# ST_LINK_V2.net
KiCad netlist of a schematic drawn in Altium Designer
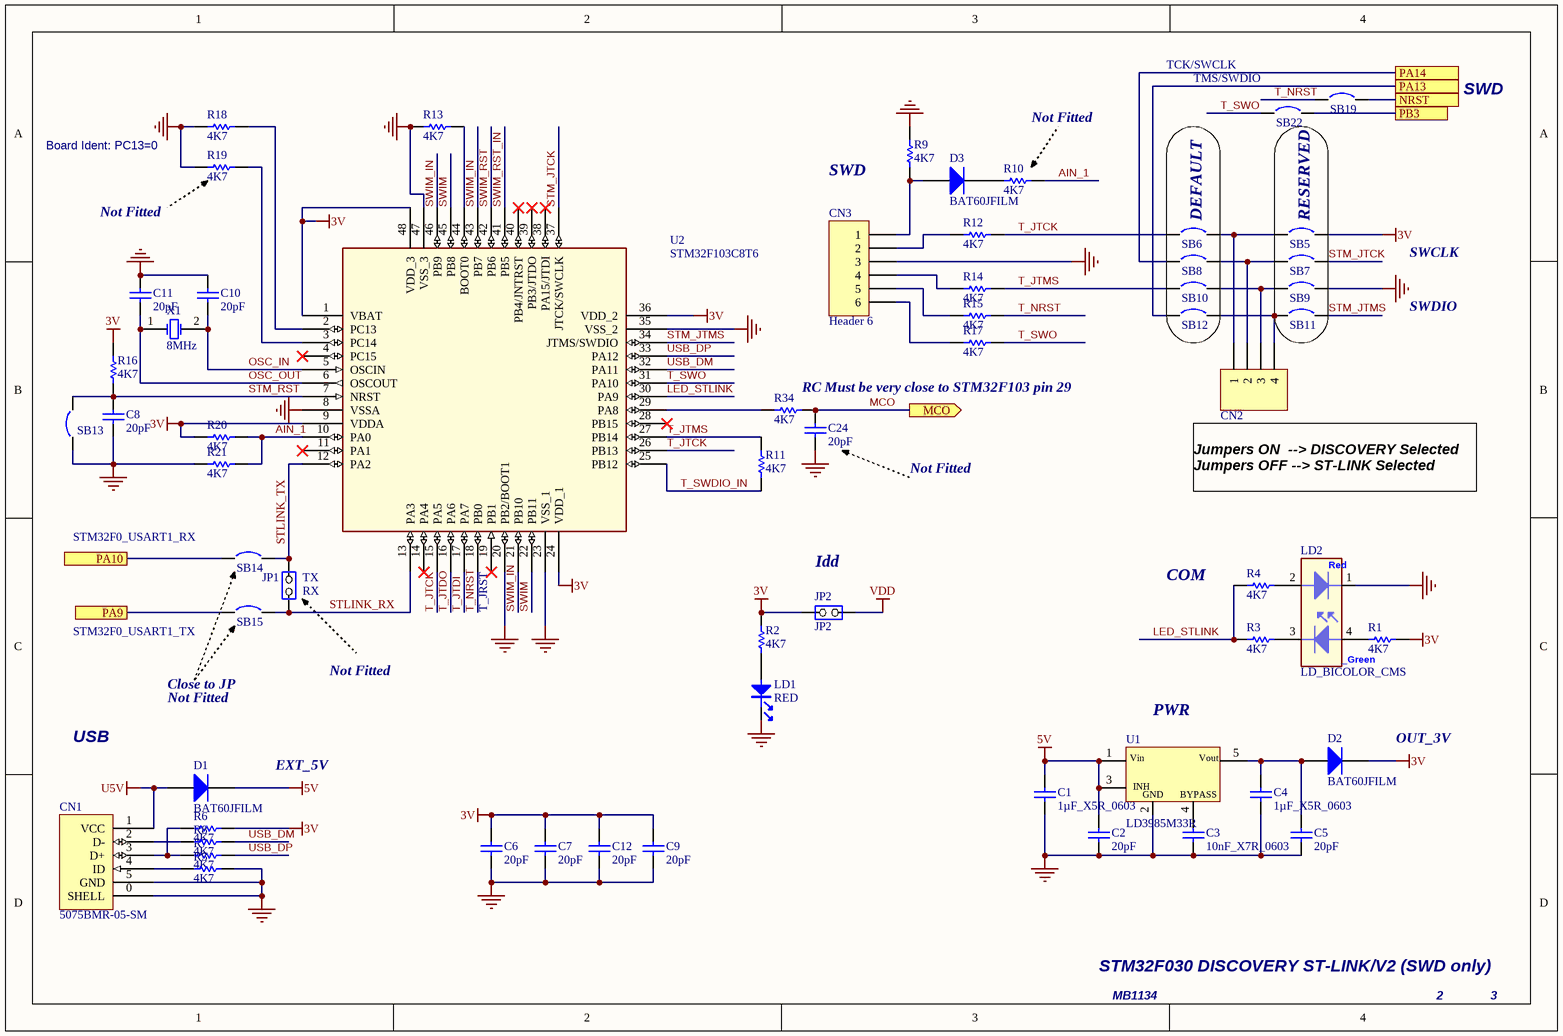
[diagram p0: ST_LINK_V2.SCHDOC]

(export (version "E")
  (design (tool "Eeschema 10.0.6"))
  (components
    (comp (ref "C1")
      (value "1µF_X5R_0603")
      (footprint "CAPC1608X90")
      (description "0603  X5R 1µF")
      (fields (field (name "TOLERANCE") "10%"))
      (libsource (lib "MB1134") (part "CAP SMD 0603  X5R 1µF 25V 10%"))
    )
    (comp (ref "C2")
      (value "20pF")
      (footprint "CAPC1608X90")
      (description "Capacitor")
      (fields (field (name "PUBLISHER") "Altium Limited"))
      (libsource (lib "MB1134") (part "Cap"))
    )
    (comp (ref "C3")
      (value "10nF_X7R_0603")
      (footprint "CAPC1608X90")
      (description "0603  X7R 10NF")
      (fields (field (name "TOLERANCE") "10%"))
      (libsource (lib "MB1134") (part "CAP SMD 0603  X7R 10000PF 50V 10%"))
    )
    (comp (ref "C4")
      (value "1µF_X5R_0603")
      (footprint "CAPC1608X90")
      (description "0603  X5R 1µF")
      (fields (field (name "TOLERANCE") "10%"))
      (libsource (lib "MB1134") (part "CAP SMD 0603  X5R 1µF 25V 10%"))
    )
    (comp (ref "C5")
      (value "20pF")
      (footprint "CAPC1608X90")
      (description "Capacitor")
      (fields (field (name "PUBLISHER") "Altium Limited"))
      (libsource (lib "MB1134") (part "Cap"))
    )
    (comp (ref "C6")
      (value "20pF")
      (footprint "CAPC1608X90")
      (description "Capacitor")
      (fields (field (name "PUBLISHER") "Altium Limited"))
      (libsource (lib "MB1134") (part "Cap"))
    )
    (comp (ref "C7")
      (value "20pF")
      (footprint "CAPC1608X90")
      (description "Capacitor")
      (fields (field (name "PUBLISHER") "Altium Limited"))
      (libsource (lib "MB1134") (part "Cap"))
    )
    (comp (ref "C8")
      (value "20pF")
      (footprint "CAPC1608X90")
      (description "Capacitor")
      (fields (field (name "PUBLISHER") "Altium Limited"))
      (libsource (lib "MB1134") (part "Cap"))
    )
    (comp (ref "C9")
      (value "20pF")
      (footprint "CAPC1608X90")
      (description "Capacitor")
      (fields (field (name "PUBLISHER") "Altium Limited"))
      (libsource (lib "MB1134") (part "Cap"))
    )
    (comp (ref "C10")
      (value "20pF")
      (footprint "CAPC1608X90")
      (description "Capacitor")
      (fields (field (name "PUBLISHER") "Altium Limited"))
      (libsource (lib "MB1134") (part "Cap"))
    )
    (comp (ref "C11")
      (value "20pF")
      (footprint "CAPC1608X90")
      (description "Capacitor")
      (fields (field (name "PUBLISHER") "Altium Limited"))
      (libsource (lib "MB1134") (part "Cap"))
    )
    (comp (ref "C12")
      (value "20pF")
      (footprint "CAPC1608X90")
      (description "Capacitor")
      (fields (field (name "PUBLISHER") "Altium Limited"))
      (libsource (lib "MB1134") (part "Cap"))
    )
    (comp (ref "C24")
      (value "20pF")
      (footprint "CAPC1608X90")
      (description "Capacitor")
      (fields (field (name "PUBLISHER") "Altium Limited"))
      (libsource (lib "MB1134") (part "Cap"))
    )
    (comp (ref "CN1")
      (value "5075BMR-05-SM")
      (footprint "AMPHENOL_10033526-N3212LF")
      (libsource (lib "MB1134") (part "USB-MINI-typeB connector"))
    )
    (comp (ref "CN2")
      (value "Header 4")
      (footprint "SAMTEC_TSW-104-23-F-S")
      (description "Header, 4-Pin")
      (fields (field (name "PUBLISHER") "Altium Limited"))
      (libsource (lib "MB1134") (part "Header 4"))
    )
    (comp (ref "CN3")
      (value "Header 6")
      (footprint "61300611121")
      (description "Header, 6-Pin")
      (fields (field (name "PUBLISHER") "Altium Limited"))
      (libsource (lib "MB1134") (part "Header 6"))
    )
    (comp (ref "D1")
      (value "BAT60JFILM")
      (footprint "SOD2613X115N")
      (fields (field (name "PUBLISHER") "Altium Limited"))
      (libsource (lib "MB1134") (part "BAT60JFILM"))
    )
    (comp (ref "D2")
      (value "BAT60JFILM")
      (footprint "SOD2613X115N")
      (fields (field (name "PUBLISHER") "Altium Limited"))
      (libsource (lib "MB1134") (part "BAT60JFILM"))
    )
    (comp (ref "D3")
      (value "BAT60JFILM")
      (footprint "SOD2613X115N")
      (fields (field (name "PUBLISHER") "Altium Limited"))
      (libsource (lib "MB1134") (part "BAT60JFILM"))
    )
    (comp (ref "JP1")
      (value "~")
      (footprint "SAMTEC_MTMM-101-10-G-D-135")
      (libsource (lib "MB1134") (part "JP2"))
    )
    (comp (ref "JP2")
      (value "JP2")
      (footprint "SAMTEC_MTMM-101-10-G-D-135")
      (libsource (lib "MB1134") (part "JP2"))
    )
    (comp (ref "LD1") (value "RED") (footprint "LED_SML-D12Y1WT86") (libsource (lib "MB1134") (part "PHOTO")))
    (comp (ref "LD2")
      (value "LD_BICOLOR_CMS")
      (footprint "LED_XZM2CRKM2DGFBB45SCCB")
      (description "Bicolor Led")
      (libsource (lib "MB1134") (part "LD_BICOLOR_CMS"))
    )
    (comp (ref "R1")
      (value "4K7")
      (footprint "RESC1005X35N")
      (description "Resistor")
      (fields (field (name "PUBLISHER") "Altium Limited"))
      (libsource (lib "MB1134") (part "res1"))
    )
    (comp (ref "R2")
      (value "4K7")
      (footprint "RESC1005X35N")
      (description "Resistor")
      (fields (field (name "PUBLISHER") "Altium Limited"))
      (libsource (lib "MB1134") (part "res1"))
    )
    (comp (ref "R3")
      (value "4K7")
      (footprint "RESC1005X35N")
      (description "Resistor")
      (fields (field (name "PUBLISHER") "Altium Limited"))
      (libsource (lib "MB1134") (part "res1"))
    )
    (comp (ref "R4")
      (value "4K7")
      (footprint "RESC1005X35N")
      (description "Resistor")
      (fields (field (name "PUBLISHER") "Altium Limited"))
      (libsource (lib "MB1134") (part "res1"))
    )
    (comp (ref "R5")
      (value "4K7")
      (footprint "RESC1005X35N")
      (description "Resistor")
      (fields (field (name "PUBLISHER") "Altium Limited"))
      (libsource (lib "MB1134") (part "res1"))
    )
    (comp (ref "R6")
      (value "4K7")
      (footprint "RESC1005X35N")
      (description "Resistor")
      (fields (field (name "PUBLISHER") "Altium Limited"))
      (libsource (lib "MB1134") (part "res1"))
    )
    (comp (ref "R7")
      (value "4K7")
      (footprint "RESC1005X35N")
      (description "Resistor")
      (fields (field (name "PUBLISHER") "Altium Limited"))
      (libsource (lib "MB1134") (part "res1"))
    )
    (comp (ref "R8")
      (value "4K7")
      (footprint "RESC1005X35N")
      (description "Resistor")
      (fields (field (name "PUBLISHER") "Altium Limited"))
      (libsource (lib "MB1134") (part "res1"))
    )
    (comp (ref "R9")
      (value "4K7")
      (footprint "RESC1005X35N")
      (description "Resistor")
      (fields (field (name "PUBLISHER") "Altium Limited"))
      (libsource (lib "MB1134") (part "res1"))
    )
    (comp (ref "R10")
      (value "4K7")
      (footprint "RESC1005X35N")
      (description "Resistor")
      (fields (field (name "PUBLISHER") "Altium Limited"))
      (libsource (lib "MB1134") (part "res1"))
    )
    (comp (ref "R11")
      (value "4K7")
      (footprint "RESC1005X35N")
      (description "Resistor")
      (fields (field (name "PUBLISHER") "Altium Limited"))
      (libsource (lib "MB1134") (part "res1"))
    )
    (comp (ref "R12")
      (value "4K7")
      (footprint "RESC1005X35N")
      (description "Resistor")
      (fields (field (name "PUBLISHER") "Altium Limited"))
      (libsource (lib "MB1134") (part "res1"))
    )
    (comp (ref "R13")
      (value "4K7")
      (footprint "RESC1005X35N")
      (description "Resistor")
      (fields (field (name "PUBLISHER") "Altium Limited"))
      (libsource (lib "MB1134") (part "res1"))
    )
    (comp (ref "R14")
      (value "4K7")
      (footprint "RESC1005X35N")
      (description "Resistor")
      (fields (field (name "PUBLISHER") "Altium Limited"))
      (libsource (lib "MB1134") (part "res1"))
    )
    (comp (ref "R15")
      (value "4K7")
      (footprint "RESC1005X35N")
      (description "Resistor")
      (fields (field (name "PUBLISHER") "Altium Limited"))
      (libsource (lib "MB1134") (part "res1"))
    )
    (comp (ref "R16")
      (value "4K7")
      (footprint "RESC1005X35N")
      (description "Resistor")
      (fields (field (name "PUBLISHER") "Altium Limited"))
      (libsource (lib "MB1134") (part "res1"))
    )
    (comp (ref "R17")
      (value "4K7")
      (footprint "RESC1005X35N")
      (description "Resistor")
      (fields (field (name "PUBLISHER") "Altium Limited"))
      (libsource (lib "MB1134") (part "res1"))
    )
    (comp (ref "R18")
      (value "4K7")
      (footprint "RESC1005X35N")
      (description "Resistor")
      (fields (field (name "PUBLISHER") "Altium Limited"))
      (libsource (lib "MB1134") (part "res1"))
    )
    (comp (ref "R19")
      (value "4K7")
      (footprint "RESC1005X35N")
      (description "Resistor")
      (fields (field (name "PUBLISHER") "Altium Limited"))
      (libsource (lib "MB1134") (part "res1"))
    )
    (comp (ref "R20")
      (value "4K7")
      (footprint "RESC1005X35N")
      (description "Resistor")
      (fields (field (name "PUBLISHER") "Altium Limited"))
      (libsource (lib "MB1134") (part "res1"))
    )
    (comp (ref "R21")
      (value "4K7")
      (footprint "RESC1005X35N")
      (description "Resistor")
      (fields (field (name "PUBLISHER") "Altium Limited"))
      (libsource (lib "MB1134") (part "res1"))
    )
    (comp (ref "R34")
      (value "4K7")
      (footprint "RESC1005X35N")
      (description "Resistor")
      (fields (field (name "PUBLISHER") "Altium Limited"))
      (libsource (lib "MB1134") (part "res1"))
    )
    (comp (ref "SB5")
      (value "Circuit Breaker")
      (footprint "RESC1005X35N")
      (fields (field (name "PUBLISHER") "Altium Limited"))
      (libsource (lib "MB1134") (part "Circuit Breaker"))
    )
    (comp (ref "SB6")
      (value "Circuit Breaker")
      (footprint "RESC1005X35N")
      (fields (field (name "PUBLISHER") "Altium Limited"))
      (libsource (lib "MB1134") (part "Circuit Breaker"))
    )
    (comp (ref "SB7")
      (value "Circuit Breaker")
      (footprint "RESC1005X35N")
      (fields (field (name "PUBLISHER") "Altium Limited"))
      (libsource (lib "MB1134") (part "Circuit Breaker"))
    )
    (comp (ref "SB8")
      (value "Circuit Breaker")
      (footprint "RESC1005X35N")
      (fields (field (name "PUBLISHER") "Altium Limited"))
      (libsource (lib "MB1134") (part "Circuit Breaker"))
    )
    (comp (ref "SB9")
      (value "Circuit Breaker")
      (footprint "RESC1005X35N")
      (fields (field (name "PUBLISHER") "Altium Limited"))
      (libsource (lib "MB1134") (part "Circuit Breaker"))
    )
    (comp (ref "SB10")
      (value "Circuit Breaker")
      (footprint "RESC1005X35N")
      (fields (field (name "PUBLISHER") "Altium Limited"))
      (libsource (lib "MB1134") (part "Circuit Breaker"))
    )
    (comp (ref "SB11")
      (value "Circuit Breaker")
      (footprint "RESC1005X35N")
      (fields (field (name "PUBLISHER") "Altium Limited"))
      (libsource (lib "MB1134") (part "Circuit Breaker"))
    )
    (comp (ref "SB12")
      (value "Circuit Breaker")
      (footprint "RESC1005X35N")
      (fields (field (name "PUBLISHER") "Altium Limited"))
      (libsource (lib "MB1134") (part "Circuit Breaker"))
    )
    (comp (ref "SB13")
      (value "Circuit Breaker")
      (footprint "RESC1005X35N")
      (fields (field (name "PUBLISHER") "Altium Limited"))
      (libsource (lib "MB1134") (part "Circuit Breaker"))
    )
    (comp (ref "SB14")
      (value "Circuit Breaker")
      (footprint "RESC1005X35N")
      (fields (field (name "PUBLISHER") "Altium Limited"))
      (libsource (lib "MB1134") (part "Circuit Breaker"))
    )
    (comp (ref "SB15")
      (value "Circuit Breaker")
      (footprint "RESC1005X35N")
      (fields (field (name "PUBLISHER") "Altium Limited"))
      (libsource (lib "MB1134") (part "Circuit Breaker"))
    )
    (comp (ref "SB19")
      (value "Circuit Breaker")
      (footprint "RESC1005X35N")
      (fields (field (name "PUBLISHER") "Altium Limited"))
      (libsource (lib "MB1134") (part "Circuit Breaker"))
    )
    (comp (ref "SB22")
      (value "Circuit Breaker")
      (footprint "RESC1005X35N")
      (fields (field (name "PUBLISHER") "Altium Limited"))
      (libsource (lib "MB1134") (part "Circuit Breaker"))
    )
    (comp (ref "U1")
      (value "LD3985M33R")
      (footprint "SOT95P280X145-5N")
      (description "Ultra low drop-low noise BiCMOS voltage, regulators low ESR capacitors compatible")
      (libsource (lib "MB1134") (part "LD3985M33R"))
    )
    (comp (ref "U2")
      (value "STM32F103C8T6")
      (footprint "QFP50P900X900X160-48N")
      (description "Medium-density performance line ARM-based 32-bit MCU with 64KB Flash, USB, CAN, 7 timers, 2 ADCs")
      (libsource (lib "MB1134") (part "STM32F103C8T6"))
    )
    (comp (ref "X1")
      (value "8MHz")
      (footprint "XTAL_ECS-080-20-5PX-TR")
      (description "Crystal Oscillator")
      (fields (field (name "PUBLISHER") "Altium Limited"))
      (libsource (lib "MB1134") (part "XTAL"))
    )
  )
  (nets
    (net (code "1") (name "/AIN_1") (class "Default")
      (node (ref "R10") (pin "2") (pinfunction "2_2") (pintype "passive"))
      (node (ref "R20") (pin "2") (pinfunction "2_2") (pintype "passive"))
      (node (ref "R21") (pin "2") (pinfunction "2_2") (pintype "passive"))
      (node (ref "U2") (pin "10") (pinfunction "PA0_10") (pintype "bidirectional"))
    )
    (net (code "2") (name "/LED_STLINK") (class "Default")
      (node (ref "R3") (pin "1") (pinfunction "1_1") (pintype "passive"))
      (node (ref "R4") (pin "1") (pinfunction "1_1") (pintype "passive"))
      (node (ref "U2") (pin "30") (pinfunction "PA9_30") (pintype "bidirectional"))
    )
    (net (code "3") (name "/MCO") (class "Default")
      (node (ref "C24") (pin "1") (pinfunction "1_1") (pintype "passive"))
      (node (ref "R34") (pin "2") (pinfunction "2_2") (pintype "passive"))
    )
    (net (code "4") (name "/NRST") (class "Default")
      (node (ref "SB19") (pin "2") (pinfunction "2_2") (pintype "passive"))
    )
    (net (code "5") (name "/OSC_IN") (class "Default")
      (node (ref "C10") (pin "2") (pinfunction "2_2") (pintype "passive"))
      (node (ref "U2") (pin "5") (pinfunction "OSCIN_5") (pintype "input"))
      (node (ref "X1") (pin "2") (pinfunction "OSC2_2") (pintype "passive"))
    )
    (net (code "6") (name "/OSC_OUT") (class "Default")
      (node (ref "C11") (pin "2") (pinfunction "2_2") (pintype "passive"))
      (node (ref "U2") (pin "6") (pinfunction "OSCOUT_6") (pintype "output"))
      (node (ref "X1") (pin "1") (pinfunction "OSC1_1") (pintype "passive"))
    )
    (net (code "7") (name "/PA9") (class "Default")
      (node (ref "SB15") (pin "1") (pinfunction "1_1") (pintype "passive"))
    )
    (net (code "8") (name "/PA10") (class "Default")
      (node (ref "SB14") (pin "1") (pinfunction "1_1") (pintype "passive"))
    )
    (net (code "9") (name "/PA13") (class "Default")
      (node (ref "SB12") (pin "1") (pinfunction "1_1") (pintype "passive"))
    )
    (net (code "10") (name "/PA14") (class "Default")
      (node (ref "SB8") (pin "1") (pinfunction "1_1") (pintype "passive"))
    )
    (net (code "11") (name "/PB3") (class "Default")
      (node (ref "SB22") (pin "2") (pinfunction "2_2") (pintype "passive"))
    )
    (net (code "12") (name "/STLINK_RX") (class "Default")
      (node (ref "JP1") (pin "1") (pinfunction "COMMON_1") (pintype "passive"))
      (node (ref "SB15") (pin "2") (pinfunction "2_2") (pintype "passive"))
      (node (ref "U2") (pin "13") (pinfunction "PA3_13") (pintype "bidirectional"))
    )
    (net (code "13") (name "/STLINK_TX") (class "Default")
      (node (ref "JP1") (pin "2") (pinfunction "NO_2") (pintype "passive"))
      (node (ref "SB14") (pin "2") (pinfunction "2_2") (pintype "passive"))
      (node (ref "U2") (pin "12") (pinfunction "PA2_12") (pintype "bidirectional"))
    )
    (net (code "14") (name "/STM_JTCK") (class "Default")
      (node (ref "SB7") (pin "2") (pinfunction "2_2") (pintype "passive"))
      (node (ref "U2") (pin "37") (pinfunction "JTCK/SWCLK_37") (pintype "bidirectional"))
    )
    (net (code "15") (name "/STM_JTMS") (class "Default")
      (node (ref "SB11") (pin "2") (pinfunction "2_2") (pintype "passive"))
      (node (ref "U2") (pin "34") (pinfunction "JTMS/SWDIO_34") (pintype "bidirectional"))
    )
    (net (code "16") (name "/STM_RST") (class "Default")
      (node (ref "C8") (pin "2") (pinfunction "2_2") (pintype "passive"))
      (node (ref "R16") (pin "1") (pinfunction "1_1") (pintype "passive"))
      (node (ref "SB13") (pin "2") (pinfunction "2_2") (pintype "passive"))
      (node (ref "U2") (pin "7") (pinfunction "NRST_7") (pintype "input"))
    )
    (net (code "17") (name "/SWIM") (class "Default")
      (node (ref "U2") (pin "22") (pinfunction "PB11_22") (pintype "bidirectional"))
      (node (ref "U2") (pin "45") (pinfunction "PB8_45") (pintype "bidirectional"))
    )
    (net (code "18") (name "/SWIM_IN") (class "Default")
      (node (ref "U2") (pin "21") (pinfunction "PB10_21") (pintype "bidirectional"))
      (node (ref "U2") (pin "43") (pinfunction "PB7_43") (pintype "bidirectional"))
      (node (ref "U2") (pin "46") (pinfunction "PB9_46") (pintype "bidirectional"))
    )
    (net (code "19") (name "/SWIM_RST") (class "Default")
      (node (ref "U2") (pin "42") (pinfunction "PB6_42") (pintype "bidirectional"))
    )
    (net (code "20") (name "/SWIM_RST_IN") (class "Default")
      (node (ref "U2") (pin "41") (pinfunction "PB5_41") (pintype "bidirectional"))
    )
    (net (code "21") (name "/T_JTCK") (class "Default")
      (node (ref "R12") (pin "2") (pinfunction "2_2") (pintype "passive"))
      (node (ref "SB6") (pin "1") (pinfunction "1_1") (pintype "passive"))
      (node (ref "U2") (pin "15") (pinfunction "PA5_15") (pintype "bidirectional"))
      (node (ref "U2") (pin "26") (pinfunction "PB13_26") (pintype "bidirectional"))
    )
    (net (code "22") (name "/T_JTDI") (class "Default")
      (node (ref "U2") (pin "17") (pinfunction "PA7_17") (pintype "bidirectional"))
    )
    (net (code "23") (name "/T_JTDO") (class "Default")
      (node (ref "U2") (pin "16") (pinfunction "PA6_16") (pintype "bidirectional"))
    )
    (net (code "24") (name "/T_JTMS") (class "Default")
      (node (ref "R11") (pin "2") (pinfunction "2_2") (pintype "passive"))
      (node (ref "R14") (pin "2") (pinfunction "2_2") (pintype "passive"))
      (node (ref "SB10") (pin "1") (pinfunction "1_1") (pintype "passive"))
      (node (ref "U2") (pin "27") (pinfunction "PB14_27") (pintype "bidirectional"))
    )
    (net (code "25") (name "/T_NRST") (class "Default")
      (node (ref "R15") (pin "2") (pinfunction "2_2") (pintype "passive"))
      (node (ref "SB19") (pin "1") (pinfunction "1_1") (pintype "passive"))
      (node (ref "U2") (pin "18") (pinfunction "PB0_18") (pintype "bidirectional"))
    )
    (net (code "26") (name "/T_SWDIO_IN") (class "Default")
      (node (ref "R11") (pin "1") (pinfunction "1_1") (pintype "passive"))
      (node (ref "U2") (pin "25") (pinfunction "PB12_25") (pintype "bidirectional"))
    )
    (net (code "27") (name "/T_SWO") (class "Default")
      (node (ref "R17") (pin "2") (pinfunction "2_2") (pintype "passive"))
      (node (ref "SB22") (pin "1") (pinfunction "1_1") (pintype "passive"))
      (node (ref "U2") (pin "31") (pinfunction "PA10_31") (pintype "bidirectional"))
    )
    (net (code "28") (name "/USB_DM") (class "Default")
      (node (ref "R8") (pin "2") (pinfunction "2_2") (pintype "passive"))
      (node (ref "U2") (pin "32") (pinfunction "PA11_32") (pintype "bidirectional"))
    )
    (net (code "29") (name "/USB_DP") (class "Default")
      (node (ref "R7") (pin "2") (pinfunction "2_2") (pintype "passive"))
      (node (ref "U2") (pin "33") (pinfunction "PA12_33") (pintype "bidirectional"))
    )
    (net (code "30") (name "3V") (class "Default")
      (node (ref "C12") (pin "1") (pinfunction "1_1") (pintype "passive"))
      (node (ref "C6") (pin "2") (pinfunction "2_2") (pintype "passive"))
      (node (ref "C7") (pin "2") (pinfunction "2_2") (pintype "passive"))
      (node (ref "C9") (pin "2") (pinfunction "2_2") (pintype "passive"))
      (node (ref "D2") (pin "2") (pinfunction "K_2") (pintype "passive"))
      (node (ref "JP2") (pin "1") (pinfunction "COMMON_1") (pintype "passive"))
      (node (ref "R1") (pin "2") (pinfunction "2_2") (pintype "passive"))
      (node (ref "R16") (pin "2") (pinfunction "2_2") (pintype "passive"))
      (node (ref "R2") (pin "2") (pinfunction "2_2") (pintype "passive"))
      (node (ref "R20") (pin "1") (pinfunction "1_1") (pintype "passive"))
      (node (ref "R6") (pin "2") (pinfunction "2_2") (pintype "passive"))
      (node (ref "SB5") (pin "2") (pinfunction "2_2") (pintype "passive"))
      (node (ref "U2") (pin "1") (pinfunction "VBAT_1") (pintype "power_in"))
      (node (ref "U2") (pin "24") (pinfunction "VDD_1_24") (pintype "power_in"))
      (node (ref "U2") (pin "36") (pinfunction "VDD_2_36") (pintype "power_in"))
      (node (ref "U2") (pin "48") (pinfunction "VDD_3_48") (pintype "power_in"))
      (node (ref "U2") (pin "9") (pinfunction "VDDA_9") (pintype "power_in"))
    )
    (net (code "31") (name "5V") (class "Default")
      (node (ref "C1") (pin "2") (pinfunction "2_2") (pintype "passive"))
      (node (ref "C2") (pin "2") (pinfunction "2_2") (pintype "passive"))
      (node (ref "D1") (pin "2") (pinfunction "K_2") (pintype "passive"))
      (node (ref "U1") (pin "1") (pinfunction "Vin_1") (pintype "passive"))
      (node (ref "U1") (pin "3") (pinfunction "CE_3") (pintype "passive"))
    )
    (net (code "32") (name "GND") (class "Default")
      (node (ref "C1") (pin "1") (pinfunction "1_1") (pintype "passive"))
      (node (ref "C10") (pin "1") (pinfunction "1_1") (pintype "passive"))
      (node (ref "C11") (pin "1") (pinfunction "1_1") (pintype "passive"))
      (node (ref "C12") (pin "2") (pinfunction "2_2") (pintype "passive"))
      (node (ref "C2") (pin "1") (pinfunction "1_1") (pintype "passive"))
      (node (ref "C24") (pin "2") (pinfunction "2_2") (pintype "passive"))
      (node (ref "C3") (pin "1") (pinfunction "1_1") (pintype "passive"))
      (node (ref "C4") (pin "2") (pinfunction "2_2") (pintype "passive"))
      (node (ref "C5") (pin "1") (pinfunction "1_1") (pintype "passive"))
      (node (ref "C6") (pin "1") (pinfunction "1_1") (pintype "passive"))
      (node (ref "C7") (pin "1") (pinfunction "1_1") (pintype "passive"))
      (node (ref "C8") (pin "1") (pinfunction "1_1") (pintype "passive"))
      (node (ref "C9") (pin "1") (pinfunction "1_1") (pintype "passive"))
      (node (ref "CN1") (pin "0") (pinfunction "SHELL_0") (pintype "power_in"))
      (node (ref "CN1") (pin "5") (pinfunction "GND_5") (pintype "power_in"))
      (node (ref "CN3") (pin "3") (pinfunction "3_3") (pintype "passive"))
      (node (ref "LD1") (pin "2") (pintype "passive"))
      (node (ref "LD2") (pin "1") (pinfunction "1_1") (pintype "passive"))
      (node (ref "R13") (pin "1") (pinfunction "1_1") (pintype "passive"))
      (node (ref "R18") (pin "1") (pinfunction "1_1") (pintype "passive"))
      (node (ref "R19") (pin "1") (pinfunction "1_1") (pintype "passive"))
      (node (ref "R21") (pin "1") (pinfunction "1_1") (pintype "passive"))
      (node (ref "R5") (pin "2") (pinfunction "2_2") (pintype "passive"))
      (node (ref "R9") (pin "2") (pinfunction "2_2") (pintype "passive"))
      (node (ref "SB13") (pin "1") (pinfunction "1_1") (pintype "passive"))
      (node (ref "SB9") (pin "2") (pinfunction "2_2") (pintype "passive"))
      (node (ref "U1") (pin "2") (pinfunction "GND_2") (pintype "passive"))
      (node (ref "U2") (pin "20") (pinfunction "PB2/BOOT1_20") (pintype "bidirectional"))
      (node (ref "U2") (pin "23") (pinfunction "VSS_1_23") (pintype "power_in"))
      (node (ref "U2") (pin "35") (pinfunction "VSS_2_35") (pintype "power_in"))
      (node (ref "U2") (pin "47") (pinfunction "VSS_3_47") (pintype "power_in"))
      (node (ref "U2") (pin "8") (pinfunction "VSSA_8") (pintype "power_in"))
    )
    (net (code "33") (name "Net-(CN1-D+)") (class "Default")
      (node (ref "CN1") (pin "3") (pinfunction "D+_3") (pintype "bidirectional"))
      (node (ref "R6") (pin "1") (pinfunction "1_1") (pintype "passive"))
      (node (ref "R7") (pin "1") (pinfunction "1_1") (pintype "passive"))
    )
    (net (code "34") (name "Net-(CN1-D-)") (class "Default")
      (node (ref "CN1") (pin "2") (pinfunction "D-_2") (pintype "bidirectional"))
      (node (ref "R8") (pin "1") (pinfunction "1_1") (pintype "passive"))
    )
    (net (code "35") (name "Net-(CN1-ID)") (class "Default")
      (node (ref "CN1") (pin "4") (pinfunction "ID_4") (pintype "input"))
      (node (ref "R5") (pin "1") (pinfunction "1_1") (pintype "passive"))
    )
    (net (code "36") (name "Net-(CN2-Pad1)") (class "Default")
      (node (ref "CN2") (pin "1") (pinfunction "1_1") (pintype "passive"))
      (node (ref "SB5") (pin "1") (pinfunction "1_1") (pintype "passive"))
      (node (ref "SB6") (pin "2") (pinfunction "2_2") (pintype "passive"))
    )
    (net (code "37") (name "Net-(CN2-Pad2)") (class "Default")
      (node (ref "CN2") (pin "2") (pinfunction "2_2") (pintype "passive"))
      (node (ref "SB7") (pin "1") (pinfunction "1_1") (pintype "passive"))
      (node (ref "SB8") (pin "2") (pinfunction "2_2") (pintype "passive"))
    )
    (net (code "38") (name "Net-(CN2-Pad3)") (class "Default")
      (node (ref "CN2") (pin "3") (pinfunction "3_3") (pintype "passive"))
      (node (ref "SB10") (pin "2") (pinfunction "2_2") (pintype "passive"))
      (node (ref "SB9") (pin "1") (pinfunction "1_1") (pintype "passive"))
    )
    (net (code "39") (name "Net-(CN2-Pad4)") (class "Default")
      (node (ref "CN2") (pin "4") (pinfunction "4_4") (pintype "passive"))
      (node (ref "SB11") (pin "1") (pinfunction "1_1") (pintype "passive"))
      (node (ref "SB12") (pin "2") (pinfunction "2_2") (pintype "passive"))
    )
    (net (code "40") (name "Net-(CN3-Pad2)") (class "Default")
      (node (ref "CN3") (pin "2") (pinfunction "2_2") (pintype "passive"))
      (node (ref "R12") (pin "1") (pinfunction "1_1") (pintype "passive"))
    )
    (net (code "41") (name "Net-(CN3-Pad4)") (class "Default")
      (node (ref "CN3") (pin "4") (pinfunction "4_4") (pintype "passive"))
      (node (ref "R14") (pin "1") (pinfunction "1_1") (pintype "passive"))
    )
    (net (code "42") (name "Net-(CN3-Pad5)") (class "Default")
      (node (ref "CN3") (pin "5") (pinfunction "5_5") (pintype "passive"))
      (node (ref "R15") (pin "1") (pinfunction "1_1") (pintype "passive"))
    )
    (net (code "43") (name "Net-(CN3-Pad6)") (class "Default")
      (node (ref "CN3") (pin "6") (pinfunction "6_6") (pintype "passive"))
      (node (ref "R17") (pin "1") (pinfunction "1_1") (pintype "passive"))
    )
    (net (code "44") (name "Net-(D2-A)") (class "Default")
      (node (ref "C4") (pin "1") (pinfunction "1_1") (pintype "passive"))
      (node (ref "C5") (pin "2") (pinfunction "2_2") (pintype "passive"))
      (node (ref "D2") (pin "1") (pinfunction "A_1") (pintype "passive"))
      (node (ref "U1") (pin "5") (pinfunction "Vout_5") (pintype "passive"))
    )
    (net (code "45") (name "Net-(D3-A)") (class "Default")
      (node (ref "CN3") (pin "1") (pinfunction "1_1") (pintype "passive"))
      (node (ref "D3") (pin "1") (pinfunction "A_1") (pintype "passive"))
      (node (ref "R9") (pin "1") (pinfunction "1_1") (pintype "passive"))
    )
    (net (code "46") (name "Net-(D3-K)") (class "Default")
      (node (ref "D3") (pin "2") (pinfunction "K_2") (pintype "passive"))
      (node (ref "R10") (pin "1") (pinfunction "1_1") (pintype "passive"))
    )
    (net (code "47") (name "Net-(LD1-Pad1)") (class "Default")
      (node (ref "LD1") (pin "1") (pintype "passive"))
      (node (ref "R2") (pin "1") (pinfunction "1_1") (pintype "passive"))
    )
    (net (code "48") (name "Net-(LD2-Pad2)") (class "Default")
      (node (ref "LD2") (pin "2") (pinfunction "2_2") (pintype "passive"))
      (node (ref "R4") (pin "2") (pinfunction "2_2") (pintype "passive"))
    )
    (net (code "49") (name "Net-(LD2-Pad3)") (class "Default")
      (node (ref "LD2") (pin "3") (pinfunction "3_3") (pintype "passive"))
      (node (ref "R3") (pin "2") (pinfunction "2_2") (pintype "passive"))
    )
    (net (code "50") (name "Net-(LD2-Pad4)") (class "Default")
      (node (ref "LD2") (pin "4") (pinfunction "4_4") (pintype "passive"))
      (node (ref "R1") (pin "1") (pinfunction "1_1") (pintype "passive"))
    )
    (net (code "51") (name "Net-(U1-BYPASS)") (class "Default")
      (node (ref "C3") (pin "2") (pinfunction "2_2") (pintype "passive"))
      (node (ref "U1") (pin "4") (pinfunction "BYPASS_4") (pintype "passive"))
    )
    (net (code "52") (name "Net-(U2-BOOT0)") (class "Default")
      (node (ref "R13") (pin "2") (pinfunction "2_2") (pintype "passive"))
      (node (ref "U2") (pin "44") (pinfunction "BOOT0_44") (pintype "bidirectional"))
    )
    (net (code "53") (name "Net-(U2-PA8)") (class "Default")
      (node (ref "R34") (pin "1") (pinfunction "1_1") (pintype "passive"))
      (node (ref "U2") (pin "29") (pinfunction "PA8_29") (pintype "bidirectional"))
    )
    (net (code "54") (name "Net-(U2-PC13)") (class "Default")
      (node (ref "R18") (pin "2") (pinfunction "2_2") (pintype "passive"))
      (node (ref "U2") (pin "2") (pinfunction "PC13_2") (pintype "bidirectional"))
    )
    (net (code "55") (name "Net-(U2-PC14)") (class "Default")
      (node (ref "R19") (pin "2") (pinfunction "2_2") (pintype "passive"))
      (node (ref "U2") (pin "3") (pinfunction "PC14_3") (pintype "bidirectional"))
    )
    (net (code "56") (name "U5V") (class "Default")
      (node (ref "CN1") (pin "1") (pinfunction "VCC_1") (pintype "power_in"))
      (node (ref "D1") (pin "1") (pinfunction "A_1") (pintype "passive"))
    )
    (net (code "57") (name "VDD") (class "Default")
      (node (ref "JP2") (pin "2") (pinfunction "NO_2") (pintype "passive"))
    )
    (net (code "58") (name "unconnected-(U2-PA1-Pad11)") (class "Default")
      (node (ref "U2") (pin "11") (pinfunction "PA1_11") (pintype "bidirectional+no_connect"))
    )
    (net (code "59") (name "unconnected-(U2-PA4-Pad14)") (class "Default")
      (node (ref "U2") (pin "14") (pinfunction "PA4_14") (pintype "bidirectional+no_connect"))
    )
    (net (code "60") (name "unconnected-(U2-PA15{slash}JTDI-Pad38)") (class "Default")
      (node (ref "U2") (pin "38") (pinfunction "PA15/JTDI_38") (pintype "bidirectional+no_connect"))
    )
    (net (code "61") (name "unconnected-(U2-PB1-Pad19)") (class "Default")
      (node (ref "U2") (pin "19") (pinfunction "PB1_19") (pintype "input+no_connect"))
    )
    (net (code "62") (name "unconnected-(U2-PB3{slash}JTDO-Pad39)") (class "Default")
      (node (ref "U2") (pin "39") (pinfunction "PB3/JTDO_39") (pintype "bidirectional+no_connect"))
    )
    (net (code "63") (name "unconnected-(U2-PB4{slash}JNTRST-Pad40)") (class "Default")
      (node (ref "U2") (pin "40") (pinfunction "PB4/JNTRST_40") (pintype "bidirectional+no_connect"))
    )
    (net (code "64") (name "unconnected-(U2-PB15-Pad28)") (class "Default")
      (node (ref "U2") (pin "28") (pinfunction "PB15_28") (pintype "bidirectional+no_connect"))
    )
    (net (code "65") (name "unconnected-(U2-PC15-Pad4)") (class "Default")
      (node (ref "U2") (pin "4") (pinfunction "PC15_4") (pintype "bidirectional+no_connect"))
    )
  )
)
